# NE556-CD4069-Synth-Toy-2.net
KiCad netlist of a schematic drawn in EAGLE
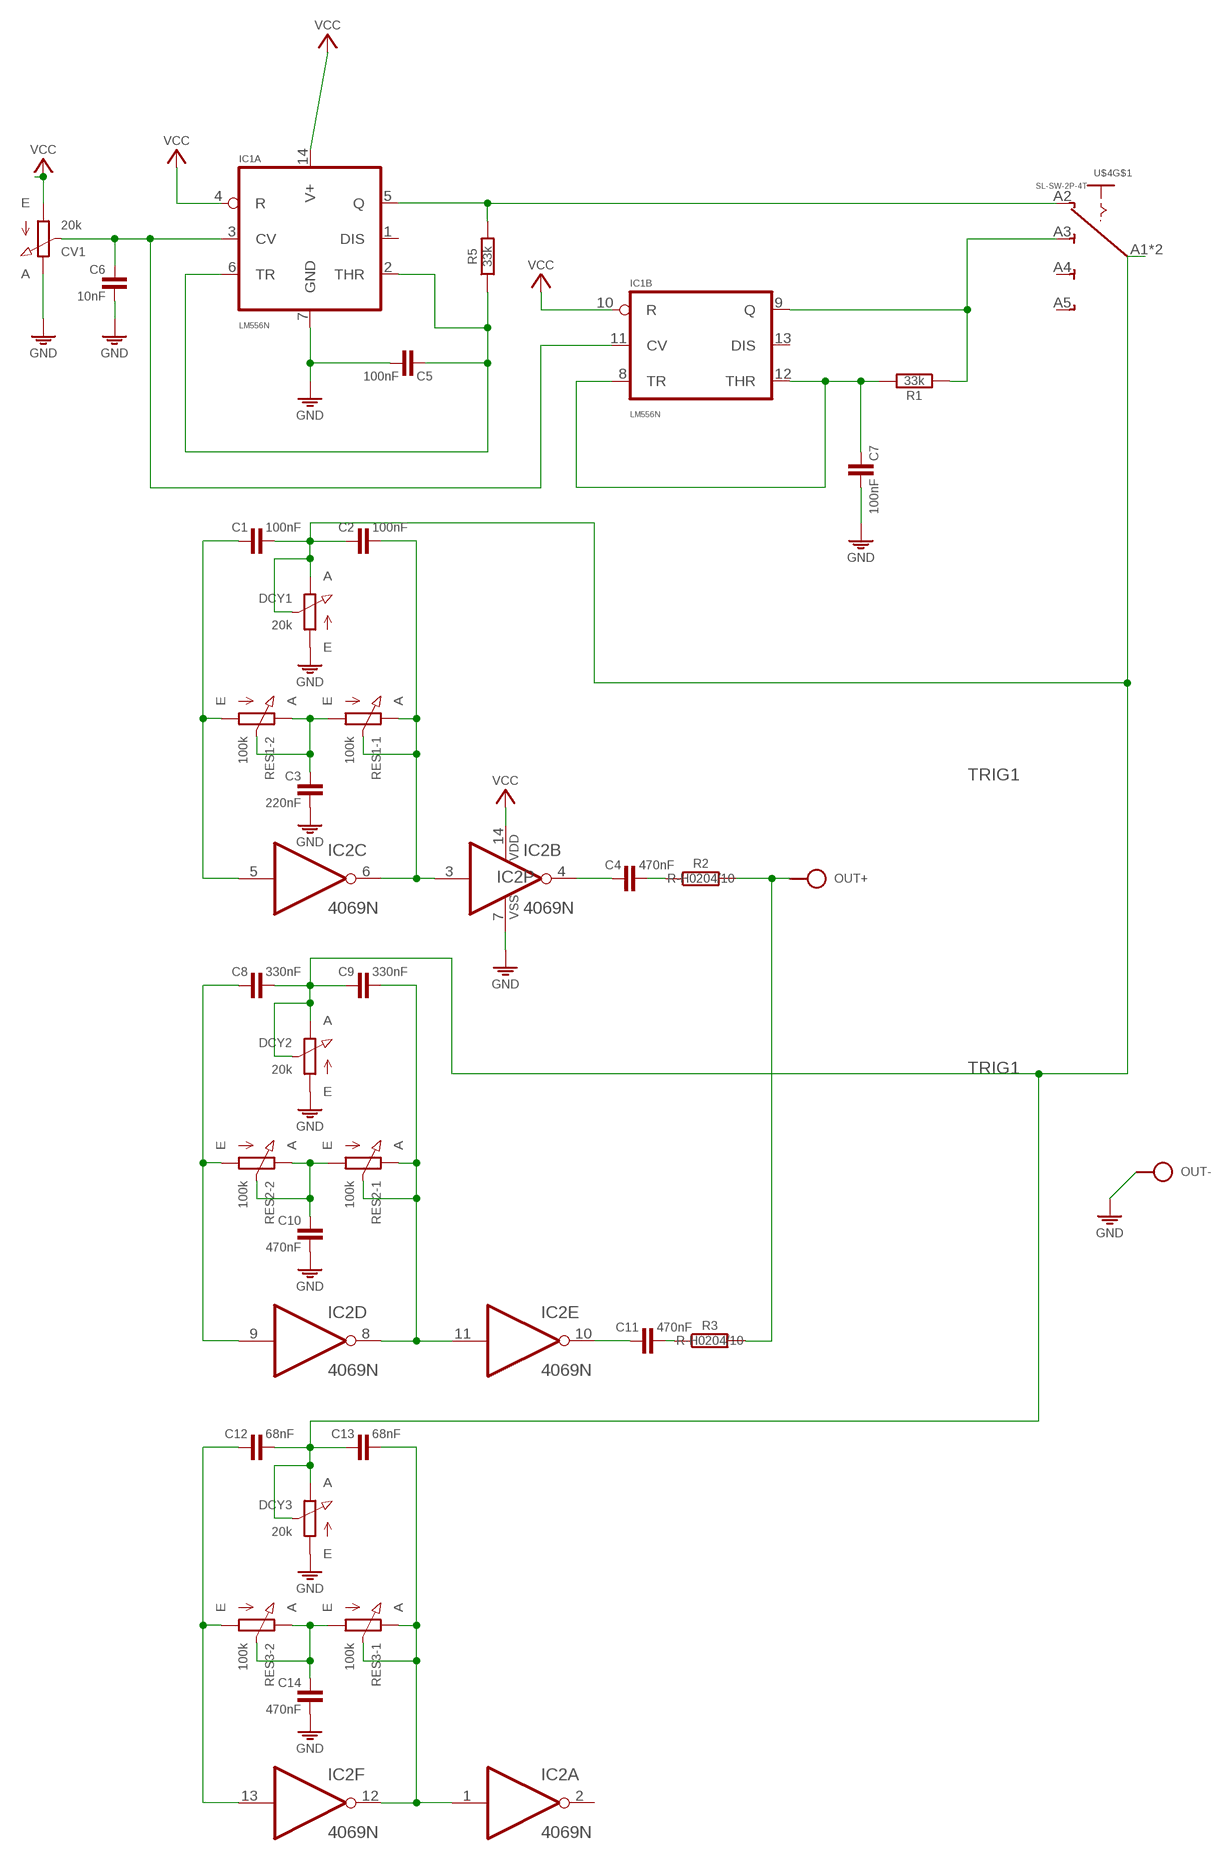
[diagram p0: schematic, sheet 1]

(export (version "E")
  (design (tool "Eeschema 10.0.6"))
  (components
    (comp (ref "C1")
      (value "100nF")
      (footprint "eagle-import:C050-024X044")
      (libsource (lib "eagle-import") (part "C-H050-024X044"))
    )
    (comp (ref "C2")
      (value "100nF")
      (footprint "eagle-import:C050-024X044")
      (libsource (lib "eagle-import") (part "C-H050-024X044"))
    )
    (comp (ref "C3")
      (value "220nF")
      (footprint "eagle-import:C050-020X044_V")
      (libsource (lib "eagle-import") (part "C050-020X044/V"))
    )
    (comp (ref "C4")
      (value "470nF")
      (footprint "eagle-import:C050-024X044")
      (libsource (lib "eagle-import") (part "C-H050-024X044"))
    )
    (comp (ref "C5")
      (value "100nF")
      (footprint "eagle-import:C050-020X044")
      (libsource (lib "eagle-import") (part "C-H050-020X044"))
    )
    (comp (ref "C6")
      (value "10nF")
      (footprint "eagle-import:C050-020X044_V")
      (libsource (lib "eagle-import") (part "C050-020X044/V"))
    )
    (comp (ref "C7")
      (value "100nF")
      (footprint "eagle-import:C050-020X044")
      (libsource (lib "eagle-import") (part "C-H050-020X044"))
    )
    (comp (ref "C8")
      (value "330nF")
      (footprint "eagle-import:C050-024X044")
      (libsource (lib "eagle-import") (part "C-H050-024X044"))
    )
    (comp (ref "C9")
      (value "330nF")
      (footprint "eagle-import:C050-024X044")
      (libsource (lib "eagle-import") (part "C-H050-024X044"))
    )
    (comp (ref "C10")
      (value "470nF")
      (footprint "eagle-import:C050-020X044_V")
      (libsource (lib "eagle-import") (part "C050-020X044/V"))
    )
    (comp (ref "C11")
      (value "470nF")
      (footprint "eagle-import:C050-024X044")
      (libsource (lib "eagle-import") (part "C-H050-024X044"))
    )
    (comp (ref "C12")
      (value "68nF")
      (footprint "eagle-import:C050-024X044")
      (libsource (lib "eagle-import") (part "C-H050-024X044"))
    )
    (comp (ref "C13")
      (value "68nF")
      (footprint "eagle-import:C050-024X044")
      (libsource (lib "eagle-import") (part "C-H050-024X044"))
    )
    (comp (ref "C14")
      (value "470nF")
      (footprint "eagle-import:C050-020X044_V")
      (libsource (lib "eagle-import") (part "C050-020X044/V"))
    )
    (comp (ref "CV1")
      (value "20k")
      (footprint "eagle-import:POT")
      (libsource (lib "eagle-import") (part "POT"))
    )
    (comp (ref "DCY1")
      (value "20k")
      (footprint "eagle-import:POT")
      (libsource (lib "eagle-import") (part "POT"))
    )
    (comp (ref "DCY2")
      (value "20k")
      (footprint "eagle-import:POT")
      (libsource (lib "eagle-import") (part "POT"))
    )
    (comp (ref "DCY3")
      (value "20k")
      (footprint "eagle-import:POT")
      (libsource (lib "eagle-import") (part "POT"))
    )
    (comp (ref "IC1")
      (value "LM556N")
      (footprint "eagle-import:DIL14")
      (libsource (lib "eagle-import") (part "556NLM"))
    )
    (comp (ref "IC2")
      (value "4069N")
      (footprint "eagle-import:DIL14")
      (libsource (lib "eagle-import") (part "4069N"))
    )
    (comp (ref "OUT")
      (value "SPAD+-+-")
      (footprint "eagle-import:SPAD+-")
      (libsource (lib "eagle-import") (part "SPAD+-+-"))
    )
    (comp (ref "R1")
      (value "33k")
      (footprint "eagle-import:0204_10-V")
      (libsource (lib "eagle-import") (part "R-H0204/10-V"))
    )
    (comp (ref "R2")
      (value "R-H0204/10")
      (footprint "eagle-import:0204_10")
      (libsource (lib "eagle-import") (part "R-H0204/10"))
    )
    (comp (ref "R3")
      (value "R-H0204/10")
      (footprint "eagle-import:0204_10")
      (libsource (lib "eagle-import") (part "R-H0204/10"))
    )
    (comp (ref "R5")
      (value "33k")
      (footprint "eagle-import:0204_10-V")
      (libsource (lib "eagle-import") (part "R-H0204/10-V"))
    )
    (comp (ref "RES1")
      (value "100k")
      (footprint "eagle-import:POT-STEREO-2X3")
      (libsource (lib "eagle-import") (part "POT-STEREO"))
    )
    (comp (ref "RES2")
      (value "100k")
      (footprint "eagle-import:POT-STEREO-2X3")
      (libsource (lib "eagle-import") (part "POT-STEREO"))
    )
    (comp (ref "RES3")
      (value "100k")
      (footprint "eagle-import:POT-STEREO-1X6-V")
      (libsource (lib "eagle-import") (part "POT-STEREO-1X6-V"))
    )
    (comp (ref "S3")
      (value "VCC_GNDPWR-L")
      (footprint "eagle-import:PWR-L")
      (libsource (lib "eagle-import") (part "VCC_GNDPWR-L"))
    )
    (comp (ref "U$4")
      (value "SL-SW-2P-4T")
      (footprint "eagle-import:SLSW-2P4T-2-H")
      (libsource (lib "eagle-import") (part "SL-SW-2P-4T"))
    )
  )
  (nets
    (net (code "1") (name "/TRIG1") (class "Default")
      (node (ref "C1") (pin "2") (pinfunction "2_2") (pintype "passive"))
      (node (ref "C12") (pin "2") (pinfunction "2_2") (pintype "passive"))
      (node (ref "C13") (pin "1") (pinfunction "1_1") (pintype "passive"))
      (node (ref "C2") (pin "1") (pinfunction "1_1") (pintype "passive"))
      (node (ref "C8") (pin "2") (pinfunction "2_2") (pintype "passive"))
      (node (ref "C9") (pin "1") (pinfunction "1_1") (pintype "passive"))
      (node (ref "DCY1") (pin "E") (pinfunction "E_E") (pintype "passive"))
      (node (ref "DCY1") (pin "S") (pinfunction "S_S") (pintype "passive"))
      (node (ref "DCY2") (pin "E") (pinfunction "E_E") (pintype "passive"))
      (node (ref "DCY2") (pin "S") (pinfunction "S_S") (pintype "passive"))
      (node (ref "DCY3") (pin "E") (pinfunction "E_E") (pintype "passive"))
      (node (ref "DCY3") (pin "S") (pinfunction "S_S") (pintype "passive"))
      (node (ref "U$4") (pin "A1") (pinfunction "P_A1") (pintype "passive"))
      (node (ref "U$4") (pin "A6") (pinfunction "P_A6") (pintype "passive"))
    )
    (net (code "2") (name "GND") (class "Default")
      (node (ref "C10") (pin "2") (pinfunction "2_2") (pintype "passive"))
      (node (ref "C14") (pin "2") (pinfunction "2_2") (pintype "passive"))
      (node (ref "C3") (pin "2") (pinfunction "2_2") (pintype "passive"))
      (node (ref "C5") (pin "2") (pinfunction "2_2") (pintype "passive"))
      (node (ref "C6") (pin "2") (pinfunction "2_2") (pintype "passive"))
      (node (ref "C7") (pin "2") (pinfunction "2_2") (pintype "passive"))
      (node (ref "CV1") (pin "E") (pinfunction "E_E") (pintype "passive"))
      (node (ref "DCY1") (pin "A") (pinfunction "A_A") (pintype "passive"))
      (node (ref "DCY2") (pin "A") (pinfunction "A_A") (pintype "passive"))
      (node (ref "DCY3") (pin "A") (pinfunction "A_A") (pintype "passive"))
      (node (ref "IC1") (pin "7") (pinfunction "GND_7") (pintype "power_in"))
      (node (ref "IC2") (pin "7") (pinfunction "VSS_7") (pintype "power_in"))
      (node (ref "OUT") (pin "1") (pinfunction "P$1_1") (pintype "passive"))
      (node (ref "S3") (pin "1") (pinfunction "GND_1") (pintype "power_in"))
    )
    (net (code "3") (name "Net-(C4-Pad2)") (class "Default")
      (node (ref "C4") (pin "2") (pinfunction "2_2") (pintype "passive"))
      (node (ref "R2") (pin "1") (pinfunction "1_1") (pintype "passive"))
    )
    (net (code "4") (name "Net-(C11-Pad2)") (class "Default")
      (node (ref "C11") (pin "2") (pinfunction "2_2") (pintype "passive"))
      (node (ref "R3") (pin "1") (pinfunction "1_1") (pintype "passive"))
    )
    (net (code "5") (name "Net-(IC1A-CV)") (class "Default")
      (node (ref "C6") (pin "1") (pinfunction "1_1") (pintype "passive"))
      (node (ref "CV1") (pin "S") (pinfunction "S_S") (pintype "passive"))
      (node (ref "IC1") (pin "11") (pinfunction "CV_11") (pintype "input"))
      (node (ref "IC1") (pin "3") (pinfunction "CV_3") (pintype "input"))
    )
    (net (code "6") (name "Net-(IC1A-Q)") (class "Default")
      (node (ref "IC1") (pin "5") (pinfunction "Q_5") (pintype "output"))
      (node (ref "R5") (pin "2") (pinfunction "2_2") (pintype "passive"))
      (node (ref "U$4") (pin "A2") (pinfunction "A_A2") (pintype "passive"))
    )
    (net (code "7") (name "Net-(IC1A-THR)") (class "Default")
      (node (ref "C5") (pin "1") (pinfunction "1_1") (pintype "passive"))
      (node (ref "IC1") (pin "2") (pinfunction "THR_2") (pintype "input"))
      (node (ref "IC1") (pin "6") (pinfunction "TR_6") (pintype "input"))
      (node (ref "R5") (pin "1") (pinfunction "1_1") (pintype "passive"))
    )
    (net (code "8") (name "Net-(IC1B-Q)") (class "Default")
      (node (ref "IC1") (pin "9") (pinfunction "Q_9") (pintype "output"))
      (node (ref "R1") (pin "1") (pinfunction "1_1") (pintype "passive"))
      (node (ref "U$4") (pin "A3") (pinfunction "B_A3") (pintype "passive"))
    )
    (net (code "9") (name "Net-(IC1B-THR)") (class "Default")
      (node (ref "C7") (pin "1") (pinfunction "1_1") (pintype "passive"))
      (node (ref "IC1") (pin "12") (pinfunction "THR_12") (pintype "input"))
      (node (ref "IC1") (pin "8") (pinfunction "TR_8") (pintype "input"))
      (node (ref "R1") (pin "2") (pinfunction "2_2") (pintype "passive"))
    )
    (net (code "10") (name "Net-(IC2A-I)") (class "Default")
      (node (ref "C13") (pin "2") (pinfunction "2_2") (pintype "passive"))
      (node (ref "IC2") (pin "1") (pinfunction "I_1") (pintype "input"))
      (node (ref "IC2") (pin "12") (pinfunction "O_12") (pintype "output"))
      (node (ref "RES3") (pin "1E") (pinfunction "E_1E") (pintype "passive"))
      (node (ref "RES3") (pin "1S") (pinfunction "S_1S") (pintype "passive"))
    )
    (net (code "11") (name "Net-(IC2B-I)") (class "Default")
      (node (ref "C2") (pin "2") (pinfunction "2_2") (pintype "passive"))
      (node (ref "IC2") (pin "3") (pinfunction "I_3") (pintype "input"))
      (node (ref "IC2") (pin "6") (pinfunction "O_6") (pintype "output"))
      (node (ref "RES1") (pin "1-E") (pinfunction "E_1-E") (pintype "passive"))
      (node (ref "RES1") (pin "1-S") (pinfunction "S_1-S") (pintype "passive"))
    )
    (net (code "12") (name "Net-(IC2B-O)") (class "Default")
      (node (ref "C4") (pin "1") (pinfunction "1_1") (pintype "passive"))
      (node (ref "IC2") (pin "4") (pinfunction "O_4") (pintype "output"))
    )
    (net (code "13") (name "Net-(IC2C-I)") (class "Default")
      (node (ref "C1") (pin "1") (pinfunction "1_1") (pintype "passive"))
      (node (ref "IC2") (pin "5") (pinfunction "I_5") (pintype "input"))
      (node (ref "RES1") (pin "2-A") (pinfunction "A_2-A") (pintype "passive"))
    )
    (net (code "14") (name "Net-(IC2D-I)") (class "Default")
      (node (ref "C8") (pin "1") (pinfunction "1_1") (pintype "passive"))
      (node (ref "IC2") (pin "9") (pinfunction "I_9") (pintype "input"))
      (node (ref "RES2") (pin "2-A") (pinfunction "A_2-A") (pintype "passive"))
    )
    (net (code "15") (name "Net-(IC2D-O)") (class "Default")
      (node (ref "C9") (pin "2") (pinfunction "2_2") (pintype "passive"))
      (node (ref "IC2") (pin "11") (pinfunction "I_11") (pintype "input"))
      (node (ref "IC2") (pin "8") (pinfunction "O_8") (pintype "output"))
      (node (ref "RES2") (pin "1-E") (pinfunction "E_1-E") (pintype "passive"))
      (node (ref "RES2") (pin "1-S") (pinfunction "S_1-S") (pintype "passive"))
    )
    (net (code "16") (name "Net-(IC2E-O)") (class "Default")
      (node (ref "C11") (pin "1") (pinfunction "1_1") (pintype "passive"))
      (node (ref "IC2") (pin "10") (pinfunction "O_10") (pintype "output"))
    )
    (net (code "17") (name "Net-(IC2F-I)") (class "Default")
      (node (ref "C12") (pin "1") (pinfunction "1_1") (pintype "passive"))
      (node (ref "IC2") (pin "13") (pinfunction "I_13") (pintype "input"))
      (node (ref "RES3") (pin "2A") (pinfunction "A_2A") (pintype "passive"))
    )
    (net (code "18") (name "Net-(OUTA-P$1)") (class "Default")
      (node (ref "OUT") (pin "2") (pinfunction "P$1_2") (pintype "passive"))
      (node (ref "R2") (pin "2") (pinfunction "2_2") (pintype "passive"))
      (node (ref "R3") (pin "2") (pinfunction "2_2") (pintype "passive"))
    )
    (net (code "19") (name "Net-(RES1A-A)") (class "Default")
      (node (ref "C3") (pin "1") (pinfunction "1_1") (pintype "passive"))
      (node (ref "RES1") (pin "1-A") (pinfunction "A_1-A") (pintype "passive"))
      (node (ref "RES1") (pin "2-E") (pinfunction "E_2-E") (pintype "passive"))
      (node (ref "RES1") (pin "2-S") (pinfunction "S_2-S") (pintype "passive"))
    )
    (net (code "20") (name "Net-(RES2A-A)") (class "Default")
      (node (ref "C10") (pin "1") (pinfunction "1_1") (pintype "passive"))
      (node (ref "RES2") (pin "1-A") (pinfunction "A_1-A") (pintype "passive"))
      (node (ref "RES2") (pin "2-E") (pinfunction "E_2-E") (pintype "passive"))
      (node (ref "RES2") (pin "2-S") (pinfunction "S_2-S") (pintype "passive"))
    )
    (net (code "21") (name "Net-(RES3A-A)") (class "Default")
      (node (ref "C14") (pin "1") (pinfunction "1_1") (pintype "passive"))
      (node (ref "RES3") (pin "1A") (pinfunction "A_1A") (pintype "passive"))
      (node (ref "RES3") (pin "2E") (pinfunction "E_2E") (pintype "passive"))
      (node (ref "RES3") (pin "2S") (pinfunction "S_2S") (pintype "passive"))
    )
    (net (code "22") (name "VCC") (class "Default")
      (node (ref "CV1") (pin "A") (pinfunction "A_A") (pintype "passive"))
      (node (ref "IC1") (pin "10") (pinfunction "R_10") (pintype "input"))
      (node (ref "IC1") (pin "14") (pinfunction "V+_14") (pintype "power_in"))
      (node (ref "IC1") (pin "4") (pinfunction "R_4") (pintype "input"))
      (node (ref "IC2") (pin "14") (pinfunction "VDD_14") (pintype "power_in"))
      (node (ref "S3") (pin "2") (pinfunction "VCC_2") (pintype "power_in"))
    )
    (net (code "23") (name "unconnected-(IC1A-DIS-Pad1)") (class "Default")
      (node (ref "IC1") (pin "1") (pinfunction "DIS_1") (pintype "passive"))
    )
    (net (code "24") (name "unconnected-(IC1B-DIS-Pad13)") (class "Default")
      (node (ref "IC1") (pin "13") (pinfunction "DIS_13") (pintype "input"))
    )
    (net (code "25") (name "unconnected-(IC2A-O-Pad2)") (class "Default")
      (node (ref "IC2") (pin "2") (pinfunction "O_2") (pintype "output"))
    )
    (net (code "26") (name "unconnected-(U$4A-C-PadA4)") (class "Default")
      (node (ref "U$4") (pin "A4") (pinfunction "C_A4") (pintype "passive"))
    )
    (net (code "27") (name "unconnected-(U$4A-D-PadA5)") (class "Default")
      (node (ref "U$4") (pin "A5") (pinfunction "D_A5") (pintype "passive"))
    )
  )
)
